# MicroSD.net
KiCad netlist of a schematic drawn in Altium Designer
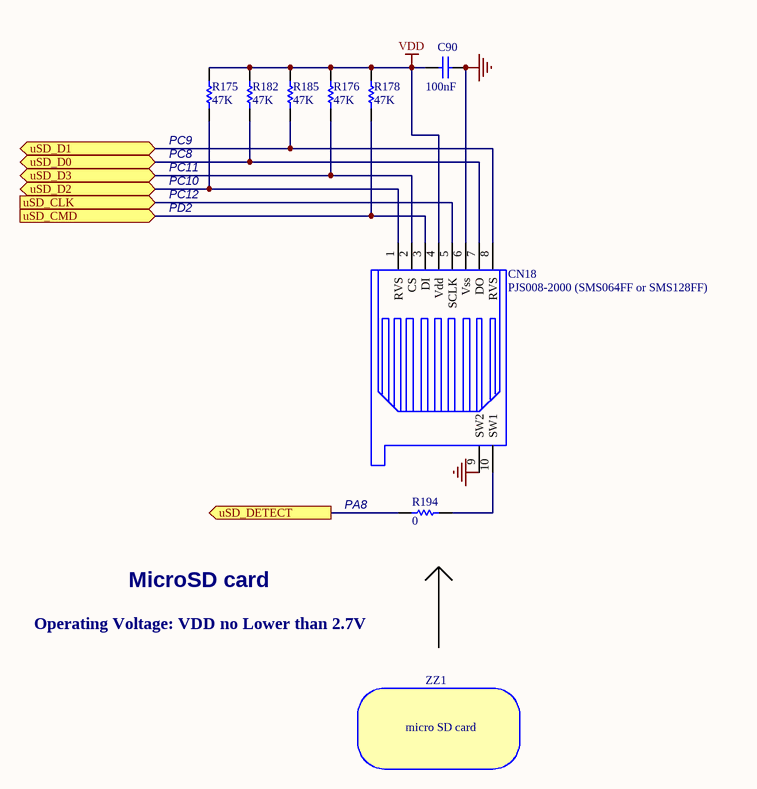
[diagram p0: MicroSD.SchDoc]

(export (version "E")
  (design (tool "Eeschema 10.0.6"))
  (components
    (comp (ref "C90")
      (value "100nF")
      (footprint "0402C")
      (description "Capacitor")
      (fields (field (name "PUBLISHER") "Altium Limited"))
      (libsource (lib "MB1144_1") (part "CAP"))
    )
    (comp (ref "CN18")
      (value "PJS008-2000 (SMS064FF or SMS128FF)")
      (footprint "MSD_PJS008_")
      (libsource (lib "MB1070") (part "SMS016AFA5E"))
    )
    (comp (ref "R175")
      (value "47K")
      (footprint "0402R")
      (description "Resistor")
      (fields (field (name "PUBLISHER") "Altium Limited"))
      (libsource (lib "Miscellaneous Devices") (part "Res1"))
    )
    (comp (ref "R176")
      (value "47K")
      (footprint "0402R")
      (description "Resistor")
      (fields (field (name "PUBLISHER") "Altium Limited"))
      (libsource (lib "Miscellaneous Devices") (part "Res1"))
    )
    (comp (ref "R178")
      (value "47K")
      (footprint "0402R")
      (description "Resistor")
      (fields (field (name "PUBLISHER") "Altium Limited"))
      (libsource (lib "Miscellaneous Devices") (part "Res1"))
    )
    (comp (ref "R182")
      (value "47K")
      (footprint "0402R")
      (description "Resistor")
      (fields (field (name "PUBLISHER") "Altium Limited"))
      (libsource (lib "Miscellaneous Devices") (part "Res1"))
    )
    (comp (ref "R185")
      (value "47K")
      (footprint "0402R")
      (description "Resistor")
      (fields (field (name "PUBLISHER") "Altium Limited"))
      (libsource (lib "Miscellaneous Devices") (part "Res1"))
    )
    (comp (ref "R194")
      (value "0")
      (footprint "0603R")
      (description "Resistor")
      (fields (field (name "PUBLISHER") "Altium Limited"))
      (libsource (lib "Miscellaneous Devices") (part "Res1"))
    )
    (comp (ref "ZZ1")
      (value "micro SD card")
      (description "4GB or more")
      (libsource (lib "Almos") (part "BoM_Item"))
    )
  )
  (nets
    (net (code "1") (name "/uSD_CLK") (class "Default")
      (node (ref "CN18") (pin "5") (pinfunction "SCLK_5") (pintype "passive"))
    )
    (net (code "2") (name "/uSD_CMD") (class "Default")
      (node (ref "CN18") (pin "3") (pinfunction "DI_3") (pintype "passive"))
      (node (ref "R178") (pin "2") (pinfunction "2_2") (pintype "passive"))
    )
    (net (code "3") (name "/uSD_D0") (class "Default")
      (node (ref "CN18") (pin "7") (pinfunction "DO_7") (pintype "passive"))
      (node (ref "R182") (pin "2") (pinfunction "2_2") (pintype "passive"))
    )
    (net (code "4") (name "/uSD_D1") (class "Default")
      (node (ref "CN18") (pin "8") (pinfunction "RVS_8") (pintype "passive"))
      (node (ref "R185") (pin "2") (pinfunction "2_2") (pintype "passive"))
    )
    (net (code "5") (name "/uSD_D2") (class "Default")
      (node (ref "CN18") (pin "1") (pinfunction "RVS_1") (pintype "passive"))
      (node (ref "R175") (pin "2") (pinfunction "2_2") (pintype "passive"))
    )
    (net (code "6") (name "/uSD_D3") (class "Default")
      (node (ref "CN18") (pin "2") (pinfunction "CS_2") (pintype "passive"))
      (node (ref "R176") (pin "2") (pinfunction "2_2") (pintype "passive"))
    )
    (net (code "7") (name "/uSD_DETECT") (class "Default")
      (node (ref "R194") (pin "1") (pinfunction "1_1") (pintype "passive"))
    )
    (net (code "8") (name "GND") (class "Default")
      (node (ref "C90") (pin "2") (pinfunction "2_2") (pintype "passive"))
      (node (ref "CN18") (pin "6") (pinfunction "Vss_6") (pintype "passive"))
      (node (ref "CN18") (pin "9") (pinfunction "SW2_9") (pintype "passive"))
    )
    (net (code "9") (name "Net-(CN18-SW1)") (class "Default")
      (node (ref "CN18") (pin "10") (pinfunction "SW1_10") (pintype "passive"))
      (node (ref "R194") (pin "2") (pinfunction "2_2") (pintype "passive"))
    )
    (net (code "10") (name "VDD") (class "Default")
      (node (ref "C90") (pin "1") (pinfunction "1_1") (pintype "passive"))
      (node (ref "CN18") (pin "4") (pinfunction "Vdd_4") (pintype "passive"))
      (node (ref "R175") (pin "1") (pinfunction "1_1") (pintype "passive"))
      (node (ref "R176") (pin "1") (pinfunction "1_1") (pintype "passive"))
      (node (ref "R178") (pin "1") (pinfunction "1_1") (pintype "passive"))
      (node (ref "R182") (pin "1") (pinfunction "1_1") (pintype "passive"))
      (node (ref "R185") (pin "1") (pinfunction "1_1") (pintype "passive"))
    )
  )
)
